# ESP_adapter_circuit_diagram.net
KiCad netlist of a schematic drawn in EAGLE
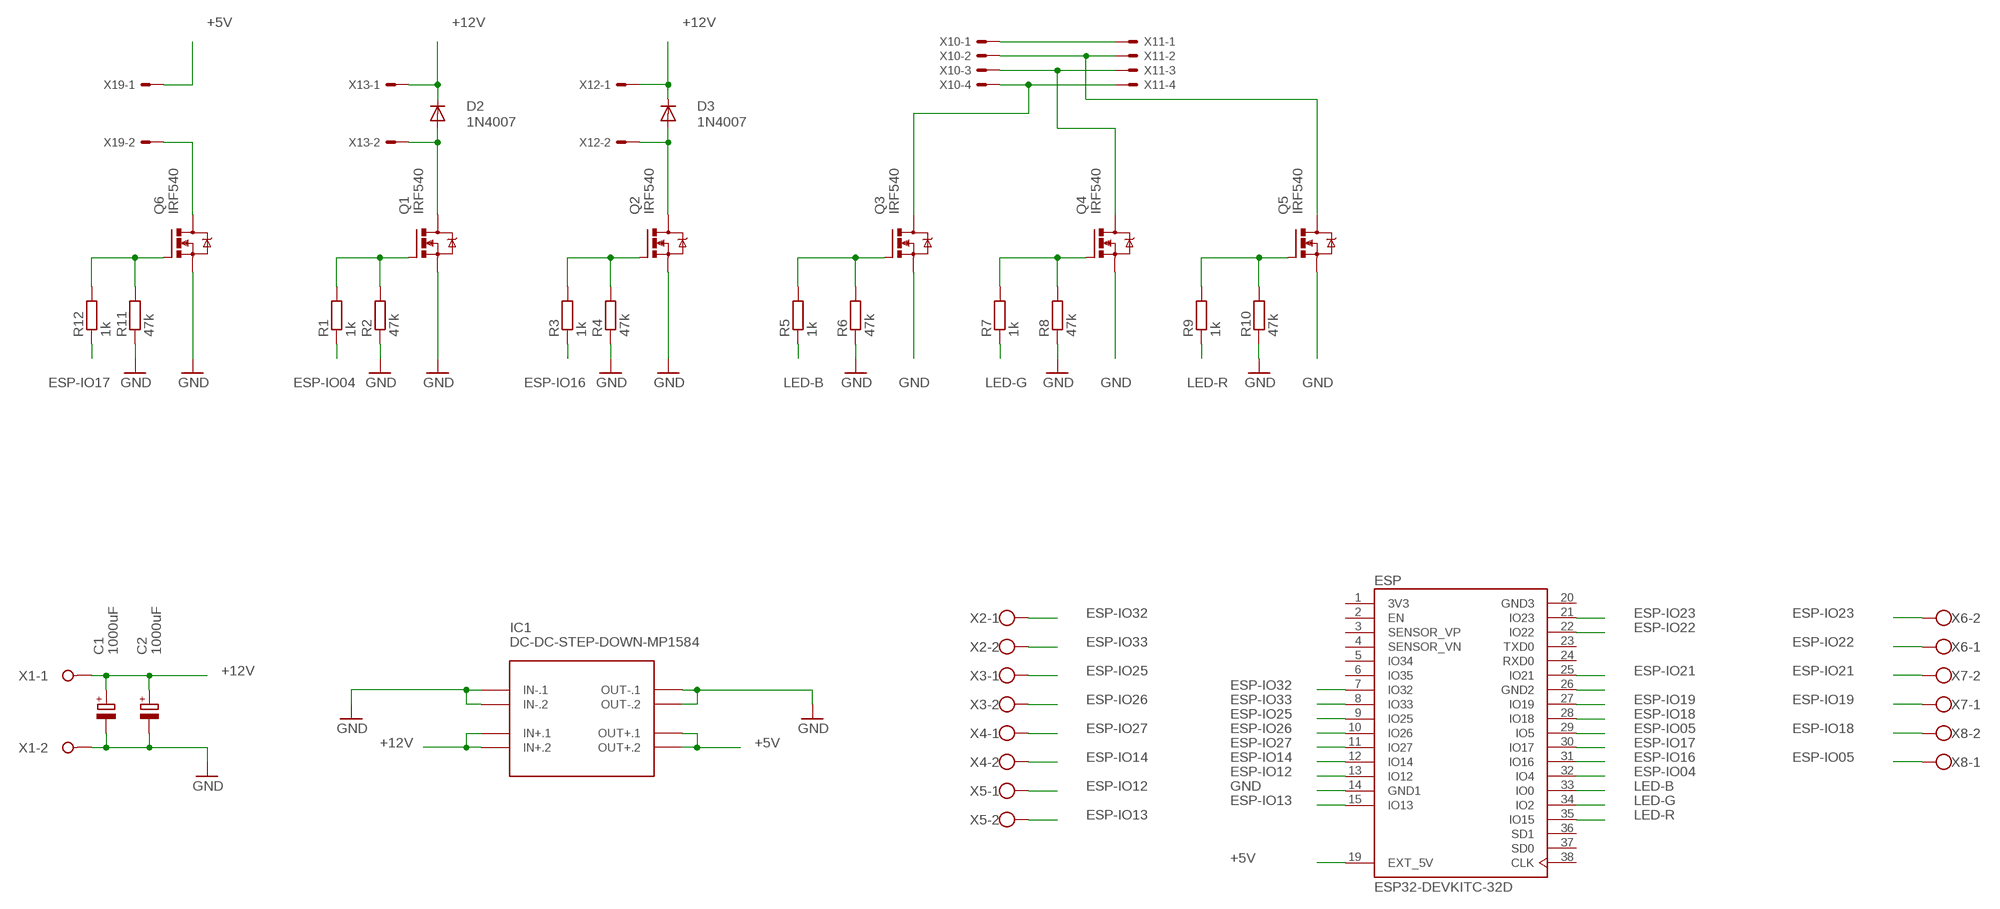
[diagram p0: schematic, sheet 1]

(export (version "E")
  (design (tool "Eeschema 10.0.6"))
  (components
    (comp (ref "C1")
      (value "1000uF")
      (footprint "eagle-import:E5-13")
      (libsource (lib "eagle-import") (part "CPOL-EUE5-13"))
    )
    (comp (ref "C2")
      (value "1000uF")
      (footprint "eagle-import:E5-13")
      (libsource (lib "eagle-import") (part "CPOL-EUE5-13"))
    )
    (comp (ref "D2")
      (value "1N4007")
      (footprint "eagle-import:DO41-10")
      (libsource (lib "eagle-import") (part "1N4004"))
    )
    (comp (ref "D3")
      (value "1N4007")
      (footprint "eagle-import:DO41-10")
      (libsource (lib "eagle-import") (part "1N4004"))
    )
    (comp (ref "ESP")
      (value "ESP32-DEVKITC-32D")
      (footprint "eagle-import:MODULE_ESP32-DEVKITC-32D")
      (fields (field (name "MF") "Espressif Systems"))
      (libsource (lib "eagle-import") (part "ESP32-DEVKITC-32D"))
    )
    (comp (ref "IC1")
      (value "DC-DC-STEP-DOWN-MP1584")
      (footprint "eagle-import:DC-DC-STEP-DOWN-MP1584")
      (libsource (lib "eagle-import") (part "DC-DC-STEP-DOWN-MP1584"))
    )
    (comp (ref "Q1")
      (value "IRF540")
      (footprint "eagle-import:TO220BV")
      (libsource (lib "eagle-import") (part "IRF540"))
    )
    (comp (ref "Q2")
      (value "IRF540")
      (footprint "eagle-import:TO220BV")
      (libsource (lib "eagle-import") (part "IRF540"))
    )
    (comp (ref "Q3")
      (value "IRF540")
      (footprint "eagle-import:TO220BV")
      (libsource (lib "eagle-import") (part "IRF540"))
    )
    (comp (ref "Q4")
      (value "IRF540")
      (footprint "eagle-import:TO220BV")
      (libsource (lib "eagle-import") (part "IRF540"))
    )
    (comp (ref "Q5")
      (value "IRF540")
      (footprint "eagle-import:TO220BV")
      (libsource (lib "eagle-import") (part "IRF540"))
    )
    (comp (ref "Q6")
      (value "IRF540")
      (footprint "eagle-import:TO220BV")
      (libsource (lib "eagle-import") (part "IRF540"))
    )
    (comp (ref "R1")
      (value "1k")
      (footprint "eagle-import:0204_7")
      (libsource (lib "eagle-import") (part "R-EU_0204/7"))
    )
    (comp (ref "R2")
      (value "47k")
      (footprint "eagle-import:0204_7")
      (libsource (lib "eagle-import") (part "R-EU_0204/7"))
    )
    (comp (ref "R3")
      (value "1k")
      (footprint "eagle-import:0204_7")
      (libsource (lib "eagle-import") (part "R-EU_0204/7"))
    )
    (comp (ref "R4")
      (value "47k")
      (footprint "eagle-import:0204_7")
      (libsource (lib "eagle-import") (part "R-EU_0204/7"))
    )
    (comp (ref "R5")
      (value "1k")
      (footprint "eagle-import:0204_7")
      (libsource (lib "eagle-import") (part "R-EU_0204/7"))
    )
    (comp (ref "R6")
      (value "47k")
      (footprint "eagle-import:0204_7")
      (libsource (lib "eagle-import") (part "R-EU_0204/7"))
    )
    (comp (ref "R7")
      (value "1k")
      (footprint "eagle-import:0204_7")
      (libsource (lib "eagle-import") (part "R-EU_0204/7"))
    )
    (comp (ref "R8")
      (value "47k")
      (footprint "eagle-import:0204_7")
      (libsource (lib "eagle-import") (part "R-EU_0204/7"))
    )
    (comp (ref "R9")
      (value "1k")
      (footprint "eagle-import:0204_7")
      (libsource (lib "eagle-import") (part "R-EU_0204/7"))
    )
    (comp (ref "R10")
      (value "47k")
      (footprint "eagle-import:0204_7")
      (libsource (lib "eagle-import") (part "R-EU_0204/7"))
    )
    (comp (ref "R11")
      (value "47k")
      (footprint "eagle-import:0204_7")
      (libsource (lib "eagle-import") (part "R-EU_0204/7"))
    )
    (comp (ref "R12")
      (value "1k")
      (footprint "eagle-import:0204_7")
      (libsource (lib "eagle-import") (part "R-EU_0204/7"))
    )
    (comp (ref "X1")
      (value "GND")
      (footprint "eagle-import:W237-132")
      (libsource (lib "eagle-import") (part "W237-02P"))
    )
    (comp (ref "X2")
      (value "W237-102")
      (footprint "eagle-import:W237-102")
      (fields (field (name "MPN") "237-102"))
      (libsource (lib "eagle-import") (part "W237-102"))
    )
    (comp (ref "X3")
      (value "W237-102")
      (footprint "eagle-import:W237-102")
      (fields (field (name "MPN") "237-102"))
      (libsource (lib "eagle-import") (part "W237-102"))
    )
    (comp (ref "X4")
      (value "W237-102")
      (footprint "eagle-import:W237-102")
      (fields (field (name "MPN") "237-102"))
      (libsource (lib "eagle-import") (part "W237-102"))
    )
    (comp (ref "X5")
      (value "W237-102")
      (footprint "eagle-import:W237-102")
      (fields (field (name "MPN") "237-102"))
      (libsource (lib "eagle-import") (part "W237-102"))
    )
    (comp (ref "X6")
      (value "W237-102")
      (footprint "eagle-import:W237-102")
      (fields (field (name "MPN") "237-102"))
      (libsource (lib "eagle-import") (part "W237-102"))
    )
    (comp (ref "X7")
      (value "W237-102")
      (footprint "eagle-import:W237-102")
      (fields (field (name "MPN") "237-102"))
      (libsource (lib "eagle-import") (part "W237-102"))
    )
    (comp (ref "X8")
      (value "W237-102")
      (footprint "eagle-import:W237-102")
      (fields (field (name "MPN") "237-102"))
      (libsource (lib "eagle-import") (part "W237-102"))
    )
    (comp (ref "X10")
      (value "22-27-2041-04")
      (footprint "eagle-import:6410-04")
      (libsource (lib "eagle-import") (part "22-?-0427-2041"))
    )
    (comp (ref "X11")
      (value "22-27-2041-04")
      (footprint "eagle-import:6410-04")
      (libsource (lib "eagle-import") (part "22-?-0427-2041"))
    )
    (comp (ref "X12")
      (value "22-27-2021-02")
      (footprint "eagle-import:6410-02")
      (libsource (lib "eagle-import") (part "22-?-0227-2021"))
    )
    (comp (ref "X13")
      (value "22-27-2021-02")
      (footprint "eagle-import:6410-02")
      (libsource (lib "eagle-import") (part "22-?-0227-2021"))
    )
    (comp (ref "X19")
      (value "22-27-2021-02")
      (footprint "eagle-import:6410-02")
      (libsource (lib "eagle-import") (part "22-?-0227-2021"))
    )
  )
  (nets
    (net (code "1") (name "/+5V") (class "Default")
      (node (ref "ESP") (pin "19") (pinfunction "EXT_5V_19") (pintype "power_in"))
      (node (ref "IC1") (pin "OUT+.1") (pinfunction "OUT+.1_OUT+.1") (pintype "bidirectional"))
      (node (ref "IC1") (pin "OUT+.2") (pinfunction "OUT+.2_OUT+.2") (pintype "bidirectional"))
      (node (ref "X19") (pin "1") (pinfunction "S_1") (pintype "passive"))
    )
    (net (code "2") (name "/+12V") (class "Default")
      (node (ref "C1") (pin "+") (pinfunction "+_+") (pintype "passive"))
      (node (ref "C2") (pin "+") (pinfunction "+_+") (pintype "passive"))
      (node (ref "D2") (pin "C") (pinfunction "C_C") (pintype "passive"))
      (node (ref "D3") (pin "C") (pinfunction "C_C") (pintype "passive"))
      (node (ref "IC1") (pin "IN+.1") (pinfunction "IN+.1_IN+.1") (pintype "bidirectional"))
      (node (ref "IC1") (pin "IN+.2") (pinfunction "IN+.2_IN+.2") (pintype "bidirectional"))
      (node (ref "X1") (pin "1") (pinfunction "KL_1") (pintype "passive"))
      (node (ref "X10") (pin "1") (pinfunction "S_1") (pintype "passive"))
      (node (ref "X11") (pin "1") (pinfunction "S_1") (pintype "passive"))
      (node (ref "X12") (pin "1") (pinfunction "S_1") (pintype "passive"))
      (node (ref "X13") (pin "1") (pinfunction "S_1") (pintype "passive"))
    )
    (net (code "3") (name "/3V3") (class "Default")
      (node (ref "ESP") (pin "1") (pinfunction "3V3_1") (pintype "power_in"))
    )
    (net (code "4") (name "/ESP-IO04") (class "Default")
      (node (ref "ESP") (pin "32") (pinfunction "IO4_32") (pintype "bidirectional"))
      (node (ref "R1") (pin "1") (pinfunction "1_1") (pintype "passive"))
    )
    (net (code "5") (name "/ESP-IO05") (class "Default")
      (node (ref "ESP") (pin "29") (pinfunction "IO5_29") (pintype "bidirectional"))
      (node (ref "X8") (pin "1") (pinfunction "KL_1") (pintype "passive"))
    )
    (net (code "6") (name "/ESP-IO12") (class "Default")
      (node (ref "ESP") (pin "13") (pinfunction "IO12_13") (pintype "bidirectional"))
      (node (ref "X5") (pin "1") (pinfunction "KL_1") (pintype "passive"))
    )
    (net (code "7") (name "/ESP-IO13") (class "Default")
      (node (ref "ESP") (pin "15") (pinfunction "IO13_15") (pintype "bidirectional"))
      (node (ref "X5") (pin "2") (pinfunction "KL_2") (pintype "passive"))
    )
    (net (code "8") (name "/ESP-IO14") (class "Default")
      (node (ref "ESP") (pin "12") (pinfunction "IO14_12") (pintype "bidirectional"))
      (node (ref "X4") (pin "2") (pinfunction "KL_2") (pintype "passive"))
    )
    (net (code "9") (name "/ESP-IO16") (class "Default")
      (node (ref "ESP") (pin "31") (pinfunction "IO16_31") (pintype "bidirectional"))
      (node (ref "R3") (pin "1") (pinfunction "1_1") (pintype "passive"))
    )
    (net (code "10") (name "/ESP-IO17") (class "Default")
      (node (ref "ESP") (pin "30") (pinfunction "IO17_30") (pintype "bidirectional"))
      (node (ref "R12") (pin "1") (pinfunction "1_1") (pintype "passive"))
    )
    (net (code "11") (name "/ESP-IO18") (class "Default")
      (node (ref "ESP") (pin "28") (pinfunction "IO18_28") (pintype "bidirectional"))
      (node (ref "X8") (pin "2") (pinfunction "KL_2") (pintype "passive"))
    )
    (net (code "12") (name "/ESP-IO19") (class "Default")
      (node (ref "ESP") (pin "27") (pinfunction "IO19_27") (pintype "bidirectional"))
      (node (ref "X7") (pin "1") (pinfunction "KL_1") (pintype "passive"))
    )
    (net (code "13") (name "/ESP-IO21") (class "Default")
      (node (ref "ESP") (pin "25") (pinfunction "IO21_25") (pintype "bidirectional"))
      (node (ref "X7") (pin "2") (pinfunction "KL_2") (pintype "passive"))
    )
    (net (code "14") (name "/ESP-IO22") (class "Default")
      (node (ref "ESP") (pin "22") (pinfunction "IO22_22") (pintype "bidirectional"))
      (node (ref "X6") (pin "1") (pinfunction "KL_1") (pintype "passive"))
    )
    (net (code "15") (name "/ESP-IO23") (class "Default")
      (node (ref "ESP") (pin "21") (pinfunction "IO23_21") (pintype "bidirectional"))
      (node (ref "X6") (pin "2") (pinfunction "KL_2") (pintype "passive"))
    )
    (net (code "16") (name "/ESP-IO25") (class "Default")
      (node (ref "ESP") (pin "9") (pinfunction "IO25_9") (pintype "bidirectional"))
      (node (ref "X3") (pin "1") (pinfunction "KL_1") (pintype "passive"))
    )
    (net (code "17") (name "/ESP-IO26") (class "Default")
      (node (ref "ESP") (pin "10") (pinfunction "IO26_10") (pintype "bidirectional"))
      (node (ref "X3") (pin "2") (pinfunction "KL_2") (pintype "passive"))
    )
    (net (code "18") (name "/ESP-IO27") (class "Default")
      (node (ref "ESP") (pin "11") (pinfunction "IO27_11") (pintype "bidirectional"))
      (node (ref "X4") (pin "1") (pinfunction "KL_1") (pintype "passive"))
    )
    (net (code "19") (name "/ESP-IO32") (class "Default")
      (node (ref "ESP") (pin "7") (pinfunction "IO32_7") (pintype "bidirectional"))
      (node (ref "X2") (pin "1") (pinfunction "KL_1") (pintype "passive"))
    )
    (net (code "20") (name "/ESP-IO33") (class "Default")
      (node (ref "ESP") (pin "8") (pinfunction "IO33_8") (pintype "bidirectional"))
      (node (ref "X2") (pin "2") (pinfunction "KL_2") (pintype "passive"))
    )
    (net (code "21") (name "/GND3") (class "Default")
      (node (ref "ESP") (pin "20") (pinfunction "GND3_20") (pintype "power_in"))
    )
    (net (code "22") (name "/LED-B") (class "Default")
      (node (ref "ESP") (pin "33") (pinfunction "IO0_33") (pintype "bidirectional"))
      (node (ref "R5") (pin "1") (pinfunction "1_1") (pintype "passive"))
    )
    (net (code "23") (name "/LED-G") (class "Default")
      (node (ref "ESP") (pin "34") (pinfunction "IO2_34") (pintype "bidirectional"))
      (node (ref "R7") (pin "1") (pinfunction "1_1") (pintype "passive"))
    )
    (net (code "24") (name "/LED-R") (class "Default")
      (node (ref "ESP") (pin "35") (pinfunction "IO15_35") (pintype "bidirectional"))
      (node (ref "R9") (pin "1") (pinfunction "1_1") (pintype "passive"))
    )
    (net (code "25") (name "GND") (class "Default")
      (node (ref "C1") (pin "-") (pinfunction "-_-") (pintype "passive"))
      (node (ref "C2") (pin "-") (pinfunction "-_-") (pintype "passive"))
      (node (ref "ESP") (pin "14") (pinfunction "GND1_14") (pintype "power_in"))
      (node (ref "IC1") (pin "IN-.1") (pinfunction "IN-.1_IN-.1") (pintype "bidirectional"))
      (node (ref "IC1") (pin "IN-.2") (pinfunction "IN-.2_IN-.2") (pintype "bidirectional"))
      (node (ref "IC1") (pin "OUT-.1") (pinfunction "OUT-.1_OUT-.1") (pintype "bidirectional"))
      (node (ref "IC1") (pin "OUT-.2") (pinfunction "OUT-.2_OUT-.2") (pintype "bidirectional"))
      (node (ref "Q1") (pin "S") (pinfunction "S_S") (pintype "passive"))
      (node (ref "Q2") (pin "S") (pinfunction "S_S") (pintype "passive"))
      (node (ref "Q3") (pin "S") (pinfunction "S_S") (pintype "passive"))
      (node (ref "Q4") (pin "S") (pinfunction "S_S") (pintype "passive"))
      (node (ref "Q5") (pin "S") (pinfunction "S_S") (pintype "passive"))
      (node (ref "Q6") (pin "S") (pinfunction "S_S") (pintype "passive"))
      (node (ref "R10") (pin "1") (pinfunction "1_1") (pintype "passive"))
      (node (ref "R11") (pin "1") (pinfunction "1_1") (pintype "passive"))
      (node (ref "R2") (pin "1") (pinfunction "1_1") (pintype "passive"))
      (node (ref "R4") (pin "1") (pinfunction "1_1") (pintype "passive"))
      (node (ref "R6") (pin "1") (pinfunction "1_1") (pintype "passive"))
      (node (ref "R8") (pin "1") (pinfunction "1_1") (pintype "passive"))
      (node (ref "X1") (pin "2") (pinfunction "KL_2") (pintype "passive"))
    )
    (net (code "26") (name "Net-(Q1-PadG)") (class "Default")
      (node (ref "Q1") (pin "G") (pinfunction "G_G") (pintype "passive"))
      (node (ref "R1") (pin "2") (pinfunction "2_2") (pintype "passive"))
      (node (ref "R2") (pin "2") (pinfunction "2_2") (pintype "passive"))
    )
    (net (code "27") (name "Net-(Q2-PadG)") (class "Default")
      (node (ref "Q2") (pin "G") (pinfunction "G_G") (pintype "passive"))
      (node (ref "R3") (pin "2") (pinfunction "2_2") (pintype "passive"))
      (node (ref "R4") (pin "2") (pinfunction "2_2") (pintype "passive"))
    )
    (net (code "28") (name "Net-(Q3-PadG)") (class "Default")
      (node (ref "Q3") (pin "G") (pinfunction "G_G") (pintype "passive"))
      (node (ref "R5") (pin "2") (pinfunction "2_2") (pintype "passive"))
      (node (ref "R6") (pin "2") (pinfunction "2_2") (pintype "passive"))
    )
    (net (code "29") (name "Net-(Q4-PadG)") (class "Default")
      (node (ref "Q4") (pin "G") (pinfunction "G_G") (pintype "passive"))
      (node (ref "R7") (pin "2") (pinfunction "2_2") (pintype "passive"))
      (node (ref "R8") (pin "2") (pinfunction "2_2") (pintype "passive"))
    )
    (net (code "30") (name "Net-(Q5-PadG)") (class "Default")
      (node (ref "Q5") (pin "G") (pinfunction "G_G") (pintype "passive"))
      (node (ref "R10") (pin "2") (pinfunction "2_2") (pintype "passive"))
      (node (ref "R9") (pin "2") (pinfunction "2_2") (pintype "passive"))
    )
    (net (code "31") (name "Net-(Q6-PadG)") (class "Default")
      (node (ref "Q6") (pin "G") (pinfunction "G_G") (pintype "passive"))
      (node (ref "R11") (pin "2") (pinfunction "2_2") (pintype "passive"))
      (node (ref "R12") (pin "2") (pinfunction "2_2") (pintype "passive"))
    )
    (net (code "32") (name "Net-(X10B-S)") (class "Default")
      (node (ref "Q5") (pin "D") (pinfunction "D_D") (pintype "passive"))
      (node (ref "X10") (pin "2") (pinfunction "S_2") (pintype "passive"))
      (node (ref "X11") (pin "2") (pinfunction "S_2") (pintype "passive"))
    )
    (net (code "33") (name "Net-(X10C-S)") (class "Default")
      (node (ref "Q4") (pin "D") (pinfunction "D_D") (pintype "passive"))
      (node (ref "X10") (pin "3") (pinfunction "S_3") (pintype "passive"))
      (node (ref "X11") (pin "3") (pinfunction "S_3") (pintype "passive"))
    )
    (net (code "34") (name "Net-(X10D-S)") (class "Default")
      (node (ref "Q3") (pin "D") (pinfunction "D_D") (pintype "passive"))
      (node (ref "X10") (pin "4") (pinfunction "S_4") (pintype "passive"))
      (node (ref "X11") (pin "4") (pinfunction "S_4") (pintype "passive"))
    )
    (net (code "35") (name "Net-(X12B-S)") (class "Default")
      (node (ref "D3") (pin "A") (pinfunction "A_A") (pintype "passive"))
      (node (ref "Q2") (pin "D") (pinfunction "D_D") (pintype "passive"))
      (node (ref "X12") (pin "2") (pinfunction "S_2") (pintype "passive"))
    )
    (net (code "36") (name "Net-(X13B-S)") (class "Default")
      (node (ref "D2") (pin "A") (pinfunction "A_A") (pintype "passive"))
      (node (ref "Q1") (pin "D") (pinfunction "D_D") (pintype "passive"))
      (node (ref "X13") (pin "2") (pinfunction "S_2") (pintype "passive"))
    )
    (net (code "37") (name "Net-(X19B-S)") (class "Default")
      (node (ref "Q6") (pin "D") (pinfunction "D_D") (pintype "passive"))
      (node (ref "X19") (pin "2") (pinfunction "S_2") (pintype "passive"))
    )
    (net (code "38") (name "unconnected-(ESP-CLK-Pad38)") (class "Default")
      (node (ref "ESP") (pin "38") (pinfunction "CLK_38") (pintype "input"))
    )
    (net (code "39") (name "unconnected-(ESP-EN-Pad2)") (class "Default")
      (node (ref "ESP") (pin "2") (pinfunction "EN_2") (pintype "input"))
    )
    (net (code "40") (name "unconnected-(ESP-GND2-Pad26)") (class "Default")
      (node (ref "ESP") (pin "26") (pinfunction "GND2_26") (pintype "power_in"))
    )
    (net (code "41") (name "unconnected-(ESP-IO34-Pad5)") (class "Default")
      (node (ref "ESP") (pin "5") (pinfunction "IO34_5") (pintype "bidirectional"))
    )
    (net (code "42") (name "unconnected-(ESP-IO35-Pad6)") (class "Default")
      (node (ref "ESP") (pin "6") (pinfunction "IO35_6") (pintype "bidirectional"))
    )
    (net (code "43") (name "unconnected-(ESP-RXD0-Pad24)") (class "Default")
      (node (ref "ESP") (pin "24") (pinfunction "RXD0_24") (pintype "input"))
    )
    (net (code "44") (name "unconnected-(ESP-SD0-Pad37)") (class "Default")
      (node (ref "ESP") (pin "37") (pinfunction "SD0_37") (pintype "bidirectional"))
    )
    (net (code "45") (name "unconnected-(ESP-SD1-Pad36)") (class "Default")
      (node (ref "ESP") (pin "36") (pinfunction "SD1_36") (pintype "bidirectional"))
    )
    (net (code "46") (name "unconnected-(ESP-SENSOR_VN-Pad4)") (class "Default")
      (node (ref "ESP") (pin "4") (pinfunction "SENSOR_VN_4") (pintype "input"))
    )
    (net (code "47") (name "unconnected-(ESP-SENSOR_VP-Pad3)") (class "Default")
      (node (ref "ESP") (pin "3") (pinfunction "SENSOR_VP_3") (pintype "input"))
    )
    (net (code "48") (name "unconnected-(ESP-TXD0-Pad23)") (class "Default")
      (node (ref "ESP") (pin "23") (pinfunction "TXD0_23") (pintype "output"))
    )
  )
)
